# NanoLiteUSB.net
KiCad netlist of a schematic drawn in EAGLE
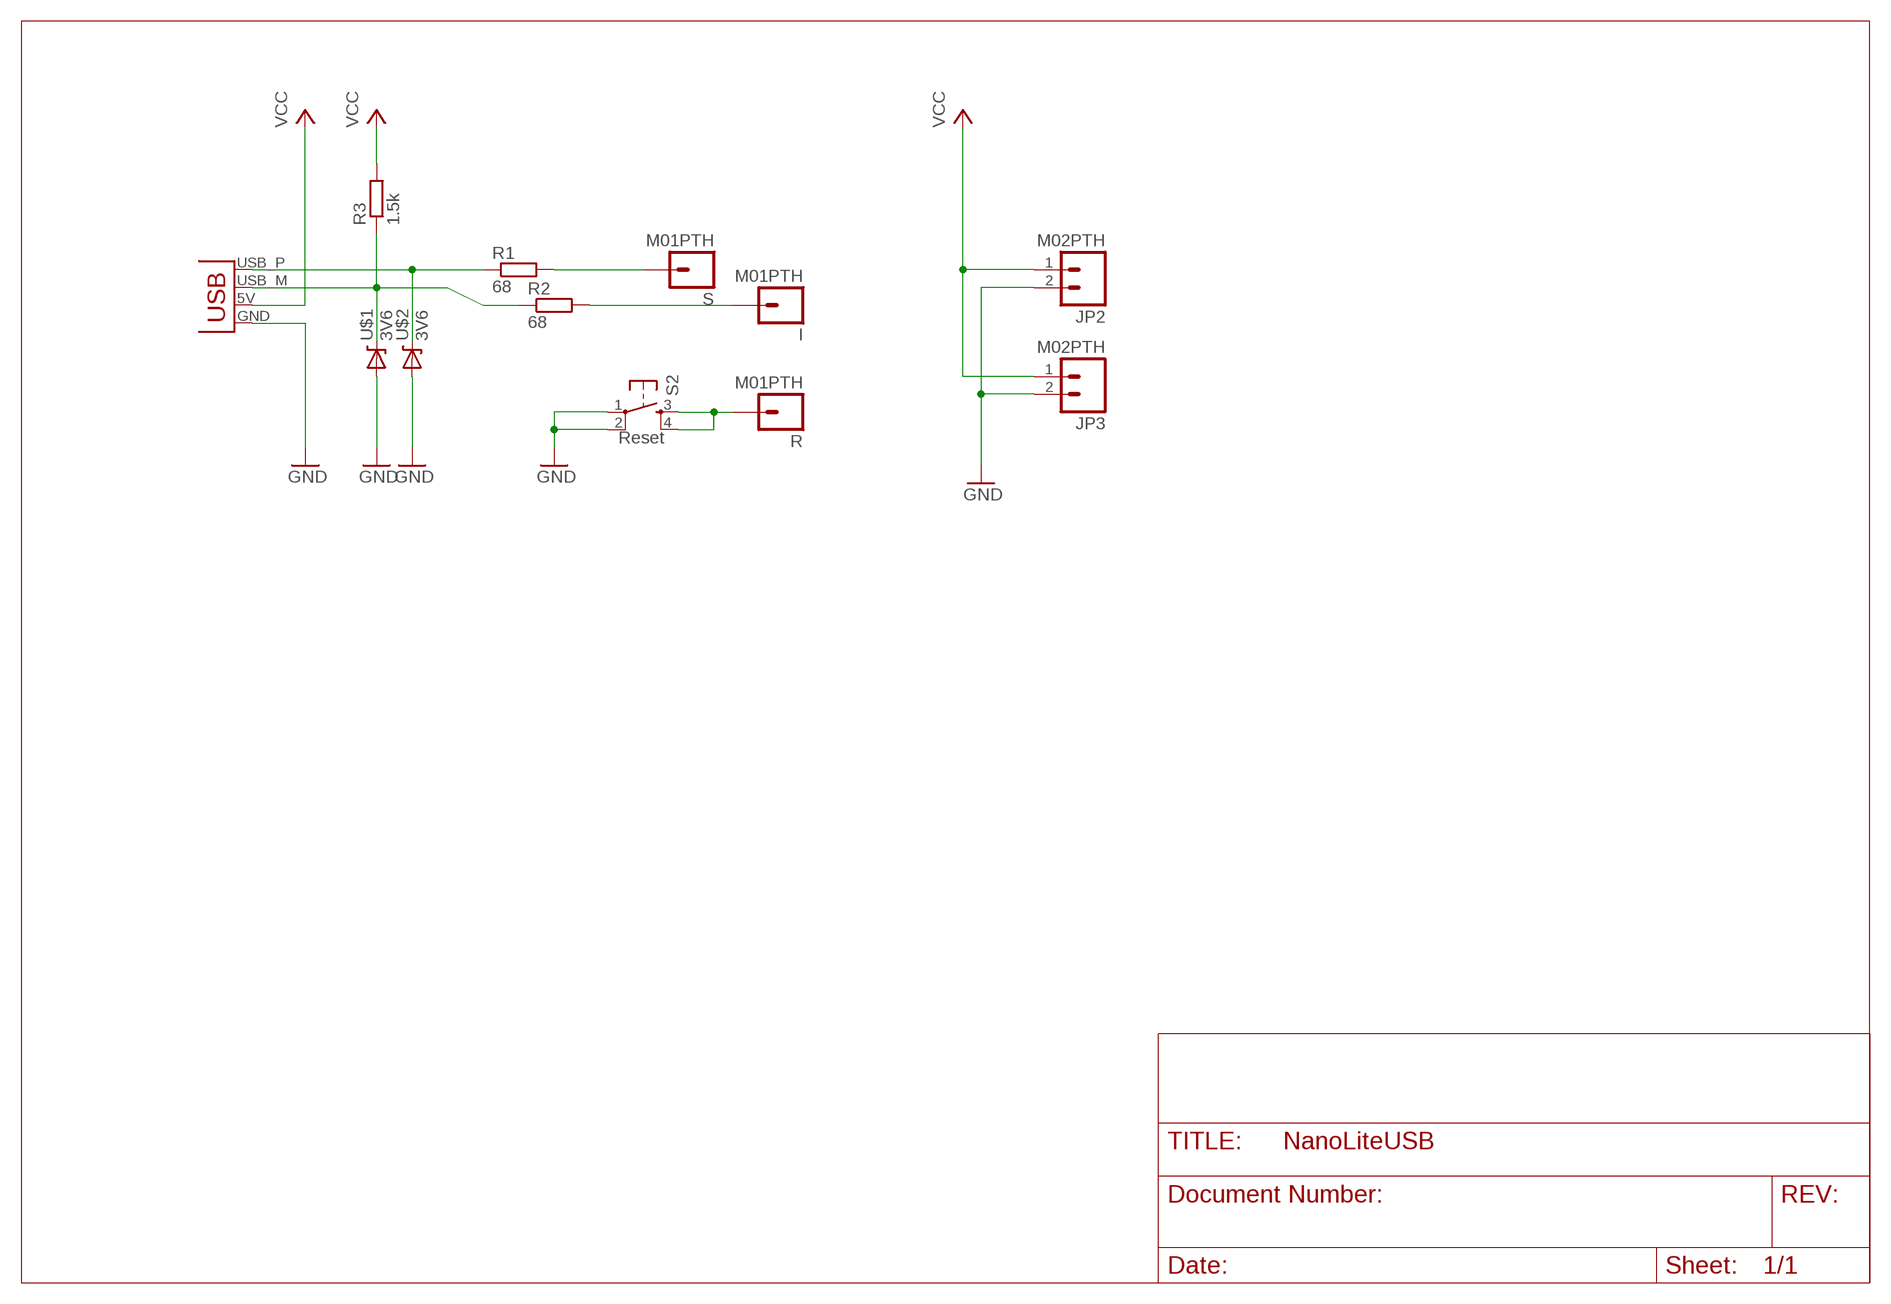
[diagram p0: schematic, sheet 1]

(export (version "E")
  (design (tool "Eeschema 10.0.6"))
  (components
    (comp (ref "I")
      (value "M01PTH")
      (footprint "eagle-import:1X01")
      (libsource (lib "eagle-import") (part "M01PTH"))
    )
    (comp (ref "JP1")
      (value "USBPCB")
      (footprint "eagle-import:USB-A-PCB")
      (libsource (lib "eagle-import") (part "USBPCB"))
    )
    (comp (ref "JP2")
      (value "M02PTH")
      (footprint "eagle-import:1X02")
      (libsource (lib "eagle-import") (part "M02PTH"))
    )
    (comp (ref "JP3")
      (value "M02PTH")
      (footprint "eagle-import:1X02")
      (libsource (lib "eagle-import") (part "M02PTH"))
    )
    (comp (ref "R")
      (value "M01PTH")
      (footprint "eagle-import:1X01")
      (libsource (lib "eagle-import") (part "M01PTH"))
    )
    (comp (ref "R1")
      (value "68")
      (footprint "eagle-import:R0603")
      (libsource (lib "eagle-import") (part "R-EU_R0603"))
    )
    (comp (ref "R2")
      (value "68")
      (footprint "eagle-import:R0603")
      (libsource (lib "eagle-import") (part "R-EU_R0603"))
    )
    (comp (ref "R3")
      (value "1.5k")
      (footprint "eagle-import:R0603")
      (libsource (lib "eagle-import") (part "R-EU_R0603"))
    )
    (comp (ref "S")
      (value "M01PTH")
      (footprint "eagle-import:1X01")
      (libsource (lib "eagle-import") (part "M01PTH"))
    )
    (comp (ref "S2")
      (value "Reset")
      (footprint "eagle-import:TACTILE_SWITCH_SMD")
      (libsource (lib "eagle-import") (part "TAC_SWITCHSMD"))
    )
    (comp (ref "U$1")
      (value "3V6")
      (footprint "eagle-import:SOD-323")
      (libsource (lib "eagle-import") (part "DIODE-ZENER-BZT52"))
    )
    (comp (ref "U$2")
      (value "3V6")
      (footprint "eagle-import:SOD-323")
      (libsource (lib "eagle-import") (part "DIODE-ZENER-BZT52"))
    )
  )
  (nets
    (net (code "1") (name "GND") (class "Default")
      (node (ref "JP1") (pin "GND") (pinfunction "GND_GND") (pintype "bidirectional"))
      (node (ref "JP2") (pin "2") (pinfunction "2_2") (pintype "passive"))
      (node (ref "JP3") (pin "2") (pinfunction "2_2") (pintype "passive"))
      (node (ref "S2") (pin "1") (pinfunction "1_1") (pintype "passive"))
      (node (ref "S2") (pin "2") (pinfunction "2_2") (pintype "passive"))
      (node (ref "U$1") (pin "2") (pinfunction "A_2") (pintype "passive"))
      (node (ref "U$2") (pin "2") (pinfunction "A_2") (pintype "passive"))
    )
    (net (code "2") (name "Net-(I-Pad1)") (class "Default")
      (node (ref "I") (pin "1") (pinfunction "1_1") (pintype "passive"))
      (node (ref "R2") (pin "2") (pinfunction "2_2") (pintype "passive"))
    )
    (net (code "3") (name "Net-(JP1-D+)") (class "Default")
      (node (ref "JP1") (pin "USB_P") (pinfunction "D+_USB_P") (pintype "bidirectional"))
      (node (ref "R1") (pin "1") (pinfunction "1_1") (pintype "passive"))
      (node (ref "U$2") (pin "1") (pinfunction "C_1") (pintype "passive"))
    )
    (net (code "4") (name "Net-(JP1-D-)") (class "Default")
      (node (ref "JP1") (pin "USB_M") (pinfunction "D-_USB_M") (pintype "bidirectional"))
      (node (ref "R2") (pin "1") (pinfunction "1_1") (pintype "passive"))
      (node (ref "R3") (pin "1") (pinfunction "1_1") (pintype "passive"))
      (node (ref "U$1") (pin "1") (pinfunction "C_1") (pintype "passive"))
    )
    (net (code "5") (name "Net-(R-Pad1)") (class "Default")
      (node (ref "R") (pin "1") (pinfunction "1_1") (pintype "passive"))
      (node (ref "S2") (pin "3") (pinfunction "3_3") (pintype "passive"))
      (node (ref "S2") (pin "4") (pinfunction "4_4") (pintype "passive"))
    )
    (net (code "6") (name "Net-(R1-Pad2)") (class "Default")
      (node (ref "R1") (pin "2") (pinfunction "2_2") (pintype "passive"))
      (node (ref "S") (pin "1") (pinfunction "1_1") (pintype "passive"))
    )
    (net (code "7") (name "VCC") (class "Default")
      (node (ref "JP1") (pin "5V") (pinfunction "VBUS_5V") (pintype "bidirectional"))
      (node (ref "JP2") (pin "1") (pinfunction "1_1") (pintype "passive"))
      (node (ref "JP3") (pin "1") (pinfunction "1_1") (pintype "passive"))
      (node (ref "R3") (pin "2") (pinfunction "2_2") (pintype "passive"))
    )
  )
)
